# DUE_shield.net
KiCad netlist of a schematic drawn in EAGLE
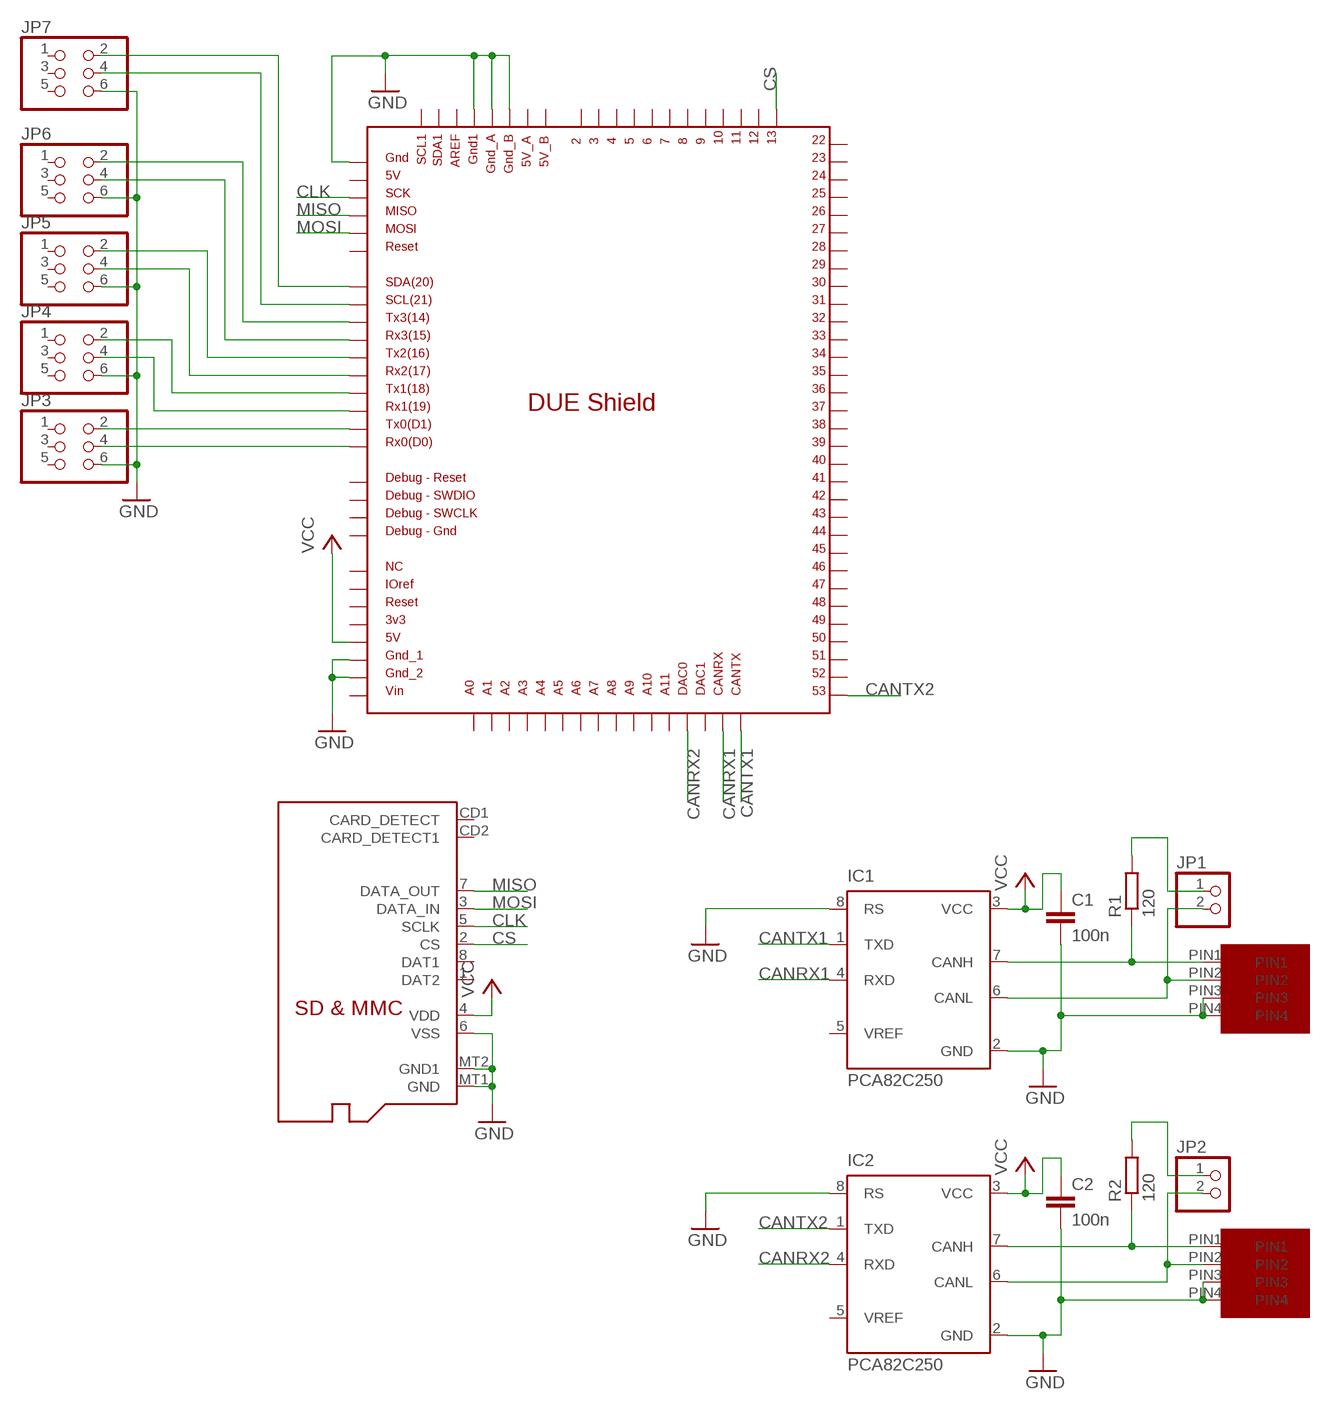
[diagram p0: schematic, sheet 1]

(export (version "E")
  (design (tool "Eeschema 10.0.6"))
  (components
    (comp (ref "C1")
      (value "100n")
      (footprint "eagle-import:C050-024X044")
      (libsource (lib "eagle-import") (part "C-EU050-024X044"))
    )
    (comp (ref "C2")
      (value "100n")
      (footprint "eagle-import:C050-024X044")
      (libsource (lib "eagle-import") (part "C-EU050-024X044"))
    )
    (comp (ref "IC1")
      (value "PCA82C250")
      (footprint "eagle-import:DIL08")
      (libsource (lib "eagle-import") (part "PCA82C250"))
    )
    (comp (ref "IC2")
      (value "PCA82C250")
      (footprint "eagle-import:DIL08")
      (libsource (lib "eagle-import") (part "PCA82C250"))
    )
    (comp (ref "JP1")
      (value "PINHD-1X2")
      (footprint "eagle-import:1X02")
      (libsource (lib "eagle-import") (part "PINHD-1X2"))
    )
    (comp (ref "JP2")
      (value "PINHD-1X2")
      (footprint "eagle-import:1X02")
      (libsource (lib "eagle-import") (part "PINHD-1X2"))
    )
    (comp (ref "JP3")
      (value "PINHD-2X3")
      (footprint "eagle-import:2X03")
      (libsource (lib "eagle-import") (part "PINHD-2X3"))
    )
    (comp (ref "JP4")
      (value "PINHD-2X3")
      (footprint "eagle-import:2X03")
      (libsource (lib "eagle-import") (part "PINHD-2X3"))
    )
    (comp (ref "JP5")
      (value "PINHD-2X3")
      (footprint "eagle-import:2X03")
      (libsource (lib "eagle-import") (part "PINHD-2X3"))
    )
    (comp (ref "JP6")
      (value "PINHD-2X3")
      (footprint "eagle-import:2X03")
      (libsource (lib "eagle-import") (part "PINHD-2X3"))
    )
    (comp (ref "JP7")
      (value "PINHD-2X3")
      (footprint "eagle-import:2X03")
      (libsource (lib "eagle-import") (part "PINHD-2X3"))
    )
    (comp (ref "R1")
      (value "120")
      (footprint "eagle-import:0204_7")
      (libsource (lib "eagle-import") (part "R-EU_0204/7"))
    )
    (comp (ref "R2")
      (value "120")
      (footprint "eagle-import:0204_7")
      (libsource (lib "eagle-import") (part "R-EU_0204/7"))
    )
    (comp (ref "U$1")
      (value "DUE(NORMAL)")
      (footprint "eagle-import:DUE(NORMAL)")
      (libsource (lib "eagle-import") (part "DUE(NORMAL)"))
    )
    (comp (ref "U$2")
      (value "MICROFIT4")
      (footprint "eagle-import:MICROFIT4SOCK")
      (libsource (lib "eagle-import") (part "MICROFIT4"))
    )
    (comp (ref "U$3")
      (value "MICROFIT4")
      (footprint "eagle-import:MICROFIT4SOCK")
      (libsource (lib "eagle-import") (part "MICROFIT4"))
    )
    (comp (ref "U$4")
      (value "MICROSD")
      (footprint "eagle-import:MICROSD")
      (libsource (lib "eagle-import") (part "MICROSD"))
    )
  )
  (nets
    (net (code "1") (name "/CANRX1") (class "Default")
      (node (ref "IC1") (pin "4") (pinfunction "RXD_4") (pintype "output"))
      (node (ref "U$1") (pin "CANRX") (pinfunction "CANRX_CANRX") (pintype "bidirectional"))
    )
    (net (code "2") (name "/CANRX2") (class "Default")
      (node (ref "IC2") (pin "4") (pinfunction "RXD_4") (pintype "output"))
      (node (ref "U$1") (pin "DAC0") (pinfunction "DAC0_DAC0") (pintype "bidirectional"))
    )
    (net (code "3") (name "/CANTX1") (class "Default")
      (node (ref "IC1") (pin "1") (pinfunction "TXD_1") (pintype "input"))
      (node (ref "U$1") (pin "CANTX") (pinfunction "CANTX_CANTX") (pintype "bidirectional"))
    )
    (net (code "4") (name "/CANTX2") (class "Default")
      (node (ref "IC2") (pin "1") (pinfunction "TXD_1") (pintype "input"))
      (node (ref "U$1") (pin "53") (pinfunction "53_53") (pintype "bidirectional"))
    )
    (net (code "5") (name "/CLK") (class "Default")
      (node (ref "U$1") (pin "SCK_ICSP") (pinfunction "SCK_ICSP_SCK_ICSP") (pintype "bidirectional"))
      (node (ref "U$4") (pin "5") (pinfunction "SCLK_5") (pintype "input"))
    )
    (net (code "6") (name "/CS") (class "Default")
      (node (ref "U$1") (pin "13") (pinfunction "13_13") (pintype "bidirectional"))
      (node (ref "U$4") (pin "2") (pinfunction "CS_2") (pintype "input"))
    )
    (net (code "7") (name "/MISO") (class "Default")
      (node (ref "U$1") (pin "MISO_ICSP") (pinfunction "MISO_ICSP_MISO_ICSP") (pintype "bidirectional"))
      (node (ref "U$4") (pin "7") (pinfunction "DATA_OUT_7") (pintype "output"))
    )
    (net (code "8") (name "/MOSI") (class "Default")
      (node (ref "U$1") (pin "MOSI_ICSP") (pinfunction "MOSI_ICSP_MOSI_ICSP") (pintype "bidirectional"))
      (node (ref "U$4") (pin "3") (pinfunction "DATA_IN_3") (pintype "input"))
    )
    (net (code "9") (name "GND") (class "Default")
      (node (ref "C1") (pin "2") (pinfunction "2_2") (pintype "passive"))
      (node (ref "C2") (pin "2") (pinfunction "2_2") (pintype "passive"))
      (node (ref "IC1") (pin "2") (pinfunction "GND_2") (pintype "power_in"))
      (node (ref "IC1") (pin "8") (pinfunction "RS_8") (pintype "input"))
      (node (ref "IC2") (pin "2") (pinfunction "GND_2") (pintype "power_in"))
      (node (ref "IC2") (pin "8") (pinfunction "RS_8") (pintype "input"))
      (node (ref "JP3") (pin "6") (pinfunction "6_6") (pintype "passive"))
      (node (ref "JP4") (pin "6") (pinfunction "6_6") (pintype "passive"))
      (node (ref "JP5") (pin "6") (pinfunction "6_6") (pintype "passive"))
      (node (ref "JP6") (pin "6") (pinfunction "6_6") (pintype "passive"))
      (node (ref "JP7") (pin "6") (pinfunction "6_6") (pintype "passive"))
      (node (ref "U$1") (pin "5V_ICSP") (pinfunction "5V_ICSP_5V_ICSP") (pintype "bidirectional"))
      (node (ref "U$1") (pin "GND1") (pinfunction "GND1_GND1") (pintype "bidirectional"))
      (node (ref "U$1") (pin "GND_1") (pinfunction "GND_1_GND_1") (pintype "bidirectional"))
      (node (ref "U$1") (pin "GND_2") (pinfunction "GND_2_GND_2") (pintype "bidirectional"))
      (node (ref "U$1") (pin "GND_A") (pinfunction "GND_A_GND_A") (pintype "bidirectional"))
      (node (ref "U$1") (pin "GND_B") (pinfunction "GND_B_GND_B") (pintype "bidirectional"))
      (node (ref "U$2") (pin "PIN3") (pinfunction "PIN3_PIN3") (pintype "bidirectional"))
      (node (ref "U$2") (pin "PIN4") (pinfunction "PIN4_PIN4") (pintype "bidirectional"))
      (node (ref "U$3") (pin "PIN3") (pinfunction "PIN3_PIN3") (pintype "bidirectional"))
      (node (ref "U$3") (pin "PIN4") (pinfunction "PIN4_PIN4") (pintype "bidirectional"))
      (node (ref "U$4") (pin "6") (pinfunction "VSS_6") (pintype "power_in"))
      (node (ref "U$4") (pin "MT1") (pinfunction "GND_MT1") (pintype "power_in"))
      (node (ref "U$4") (pin "MT2") (pinfunction "GND1_MT2") (pintype "power_in"))
    )
    (net (code "10") (name "Net-(IC1-CANH)") (class "Default")
      (node (ref "IC1") (pin "7") (pinfunction "CANH_7") (pintype "bidirectional"))
      (node (ref "R1") (pin "1") (pinfunction "1_1") (pintype "passive"))
      (node (ref "U$2") (pin "PIN1") (pinfunction "PIN1_PIN1") (pintype "bidirectional"))
    )
    (net (code "11") (name "Net-(IC1-CANL)") (class "Default")
      (node (ref "IC1") (pin "6") (pinfunction "CANL_6") (pintype "bidirectional"))
      (node (ref "JP1") (pin "2") (pinfunction "2_2") (pintype "passive"))
      (node (ref "U$2") (pin "PIN2") (pinfunction "PIN2_PIN2") (pintype "bidirectional"))
    )
    (net (code "12") (name "Net-(IC2-CANH)") (class "Default")
      (node (ref "IC2") (pin "7") (pinfunction "CANH_7") (pintype "bidirectional"))
      (node (ref "R2") (pin "1") (pinfunction "1_1") (pintype "passive"))
      (node (ref "U$3") (pin "PIN1") (pinfunction "PIN1_PIN1") (pintype "bidirectional"))
    )
    (net (code "13") (name "Net-(IC2-CANL)") (class "Default")
      (node (ref "IC2") (pin "6") (pinfunction "CANL_6") (pintype "bidirectional"))
      (node (ref "JP2") (pin "2") (pinfunction "2_2") (pintype "passive"))
      (node (ref "U$3") (pin "PIN2") (pinfunction "PIN2_PIN2") (pintype "bidirectional"))
    )
    (net (code "14") (name "Net-(JP1-Pad1)") (class "Default")
      (node (ref "JP1") (pin "1") (pinfunction "1_1") (pintype "passive"))
      (node (ref "R1") (pin "2") (pinfunction "2_2") (pintype "passive"))
    )
    (net (code "15") (name "Net-(JP2-Pad1)") (class "Default")
      (node (ref "JP2") (pin "1") (pinfunction "1_1") (pintype "passive"))
      (node (ref "R2") (pin "2") (pinfunction "2_2") (pintype "passive"))
    )
    (net (code "16") (name "Net-(JP3-Pad2)") (class "Default")
      (node (ref "JP3") (pin "2") (pinfunction "2_2") (pintype "passive"))
      (node (ref "U$1") (pin "TX0") (pinfunction "TX0_TX0") (pintype "bidirectional"))
    )
    (net (code "17") (name "Net-(JP3-Pad4)") (class "Default")
      (node (ref "JP3") (pin "4") (pinfunction "4_4") (pintype "passive"))
      (node (ref "U$1") (pin "RX0") (pinfunction "RX0_RX0") (pintype "bidirectional"))
    )
    (net (code "18") (name "Net-(JP4-Pad2)") (class "Default")
      (node (ref "JP4") (pin "2") (pinfunction "2_2") (pintype "passive"))
      (node (ref "U$1") (pin "TX1") (pinfunction "TX1_TX1") (pintype "bidirectional"))
    )
    (net (code "19") (name "Net-(JP4-Pad4)") (class "Default")
      (node (ref "JP4") (pin "4") (pinfunction "4_4") (pintype "passive"))
      (node (ref "U$1") (pin "RX1") (pinfunction "RX1_RX1") (pintype "bidirectional"))
    )
    (net (code "20") (name "Net-(JP5-Pad2)") (class "Default")
      (node (ref "JP5") (pin "2") (pinfunction "2_2") (pintype "passive"))
      (node (ref "U$1") (pin "TX2") (pinfunction "TX2_TX2") (pintype "bidirectional"))
    )
    (net (code "21") (name "Net-(JP5-Pad4)") (class "Default")
      (node (ref "JP5") (pin "4") (pinfunction "4_4") (pintype "passive"))
      (node (ref "U$1") (pin "RX2") (pinfunction "RX2_RX2") (pintype "bidirectional"))
    )
    (net (code "22") (name "Net-(JP6-Pad2)") (class "Default")
      (node (ref "JP6") (pin "2") (pinfunction "2_2") (pintype "passive"))
      (node (ref "U$1") (pin "TX3") (pinfunction "TX3_TX3") (pintype "bidirectional"))
    )
    (net (code "23") (name "Net-(JP6-Pad4)") (class "Default")
      (node (ref "JP6") (pin "4") (pinfunction "4_4") (pintype "passive"))
      (node (ref "U$1") (pin "RX3") (pinfunction "RX3_RX3") (pintype "bidirectional"))
    )
    (net (code "24") (name "Net-(JP7-Pad2)") (class "Default")
      (node (ref "JP7") (pin "2") (pinfunction "2_2") (pintype "passive"))
      (node (ref "U$1") (pin "SDA") (pinfunction "SDA_SDA") (pintype "bidirectional"))
    )
    (net (code "25") (name "Net-(JP7-Pad4)") (class "Default")
      (node (ref "JP7") (pin "4") (pinfunction "4_4") (pintype "passive"))
      (node (ref "U$1") (pin "SCL") (pinfunction "SCL_SCL") (pintype "bidirectional"))
    )
    (net (code "26") (name "VCC") (class "Default")
      (node (ref "C1") (pin "1") (pinfunction "1_1") (pintype "passive"))
      (node (ref "C2") (pin "1") (pinfunction "1_1") (pintype "passive"))
      (node (ref "IC1") (pin "3") (pinfunction "VCC_3") (pintype "power_in"))
      (node (ref "IC2") (pin "3") (pinfunction "VCC_3") (pintype "power_in"))
      (node (ref "U$1") (pin "5V") (pinfunction "5V_5V") (pintype "bidirectional"))
      (node (ref "U$4") (pin "4") (pinfunction "VDD_4") (pintype "power_in"))
    )
    (net (code "27") (name "unconnected-(IC1-VREF-Pad5)") (class "Default")
      (node (ref "IC1") (pin "5") (pinfunction "VREF_5") (pintype "output"))
    )
    (net (code "28") (name "unconnected-(IC2-VREF-Pad5)") (class "Default")
      (node (ref "IC2") (pin "5") (pinfunction "VREF_5") (pintype "output"))
    )
    (net (code "29") (name "unconnected-(JP3-Pad1)") (class "Default")
      (node (ref "JP3") (pin "1") (pinfunction "1_1") (pintype "passive"))
    )
    (net (code "30") (name "unconnected-(JP3-Pad3)") (class "Default")
      (node (ref "JP3") (pin "3") (pinfunction "3_3") (pintype "passive"))
    )
    (net (code "31") (name "unconnected-(JP3-Pad5)") (class "Default")
      (node (ref "JP3") (pin "5") (pinfunction "5_5") (pintype "passive"))
    )
    (net (code "32") (name "unconnected-(JP4-Pad1)") (class "Default")
      (node (ref "JP4") (pin "1") (pinfunction "1_1") (pintype "passive"))
    )
    (net (code "33") (name "unconnected-(JP4-Pad3)") (class "Default")
      (node (ref "JP4") (pin "3") (pinfunction "3_3") (pintype "passive"))
    )
    (net (code "34") (name "unconnected-(JP4-Pad5)") (class "Default")
      (node (ref "JP4") (pin "5") (pinfunction "5_5") (pintype "passive"))
    )
    (net (code "35") (name "unconnected-(JP5-Pad1)") (class "Default")
      (node (ref "JP5") (pin "1") (pinfunction "1_1") (pintype "passive"))
    )
    (net (code "36") (name "unconnected-(JP5-Pad3)") (class "Default")
      (node (ref "JP5") (pin "3") (pinfunction "3_3") (pintype "passive"))
    )
    (net (code "37") (name "unconnected-(JP5-Pad5)") (class "Default")
      (node (ref "JP5") (pin "5") (pinfunction "5_5") (pintype "passive"))
    )
    (net (code "38") (name "unconnected-(JP6-Pad1)") (class "Default")
      (node (ref "JP6") (pin "1") (pinfunction "1_1") (pintype "passive"))
    )
    (net (code "39") (name "unconnected-(JP6-Pad3)") (class "Default")
      (node (ref "JP6") (pin "3") (pinfunction "3_3") (pintype "passive"))
    )
    (net (code "40") (name "unconnected-(JP6-Pad5)") (class "Default")
      (node (ref "JP6") (pin "5") (pinfunction "5_5") (pintype "passive"))
    )
    (net (code "41") (name "unconnected-(JP7-Pad1)") (class "Default")
      (node (ref "JP7") (pin "1") (pinfunction "1_1") (pintype "passive"))
    )
    (net (code "42") (name "unconnected-(JP7-Pad3)") (class "Default")
      (node (ref "JP7") (pin "3") (pinfunction "3_3") (pintype "passive"))
    )
    (net (code "43") (name "unconnected-(JP7-Pad5)") (class "Default")
      (node (ref "JP7") (pin "5") (pinfunction "5_5") (pintype "passive"))
    )
    (net (code "44") (name "unconnected-(U$1-Pad2)") (class "Default")
      (node (ref "U$1") (pin "2") (pinfunction "2_2") (pintype "bidirectional"))
    )
    (net (code "45") (name "unconnected-(U$1-Pad3)") (class "Default")
      (node (ref "U$1") (pin "3") (pinfunction "3_3") (pintype "bidirectional"))
    )
    (net (code "46") (name "unconnected-(U$1-Pad3V3)") (class "Default")
      (node (ref "U$1") (pin "3V3") (pinfunction "3V3_3V3") (pintype "bidirectional"))
    )
    (net (code "47") (name "unconnected-(U$1-Pad4)") (class "Default")
      (node (ref "U$1") (pin "4") (pinfunction "4_4") (pintype "bidirectional"))
    )
    (net (code "48") (name "unconnected-(U$1-Pad5)") (class "Default")
      (node (ref "U$1") (pin "5") (pinfunction "5_5") (pintype "bidirectional"))
    )
    (net (code "49") (name "unconnected-(U$1-Pad5V_A)") (class "Default")
      (node (ref "U$1") (pin "5V_A") (pinfunction "5V_A_5V_A") (pintype "bidirectional"))
    )
    (net (code "50") (name "unconnected-(U$1-Pad5V_B)") (class "Default")
      (node (ref "U$1") (pin "5V_B") (pinfunction "5V_B_5V_B") (pintype "bidirectional"))
    )
    (net (code "51") (name "unconnected-(U$1-Pad6)") (class "Default")
      (node (ref "U$1") (pin "6") (pinfunction "6_6") (pintype "bidirectional"))
    )
    (net (code "52") (name "unconnected-(U$1-Pad7)") (class "Default")
      (node (ref "U$1") (pin "7") (pinfunction "7_7") (pintype "bidirectional"))
    )
    (net (code "53") (name "unconnected-(U$1-Pad8)") (class "Default")
      (node (ref "U$1") (pin "8") (pinfunction "8_8") (pintype "bidirectional"))
    )
    (net (code "54") (name "unconnected-(U$1-Pad9)") (class "Default")
      (node (ref "U$1") (pin "9") (pinfunction "9_9") (pintype "bidirectional"))
    )
    (net (code "55") (name "unconnected-(U$1-Pad10)") (class "Default")
      (node (ref "U$1") (pin "10") (pinfunction "10_10") (pintype "bidirectional"))
    )
    (net (code "56") (name "unconnected-(U$1-Pad11)") (class "Default")
      (node (ref "U$1") (pin "11") (pinfunction "11_11") (pintype "bidirectional"))
    )
    (net (code "57") (name "unconnected-(U$1-Pad12)") (class "Default")
      (node (ref "U$1") (pin "12") (pinfunction "12_12") (pintype "bidirectional"))
    )
    (net (code "58") (name "unconnected-(U$1-Pad22)") (class "Default")
      (node (ref "U$1") (pin "22") (pinfunction "22_22") (pintype "bidirectional"))
    )
    (net (code "59") (name "unconnected-(U$1-Pad23)") (class "Default")
      (node (ref "U$1") (pin "23") (pinfunction "23_23") (pintype "bidirectional"))
    )
    (net (code "60") (name "unconnected-(U$1-Pad24)") (class "Default")
      (node (ref "U$1") (pin "24") (pinfunction "24_24") (pintype "bidirectional"))
    )
    (net (code "61") (name "unconnected-(U$1-Pad25)") (class "Default")
      (node (ref "U$1") (pin "25") (pinfunction "25_25") (pintype "bidirectional"))
    )
    (net (code "62") (name "unconnected-(U$1-Pad26)") (class "Default")
      (node (ref "U$1") (pin "26") (pinfunction "26_26") (pintype "bidirectional"))
    )
    (net (code "63") (name "unconnected-(U$1-Pad27)") (class "Default")
      (node (ref "U$1") (pin "27") (pinfunction "27_27") (pintype "bidirectional"))
    )
    (net (code "64") (name "unconnected-(U$1-Pad28)") (class "Default")
      (node (ref "U$1") (pin "28") (pinfunction "28_28") (pintype "bidirectional"))
    )
    (net (code "65") (name "unconnected-(U$1-Pad29)") (class "Default")
      (node (ref "U$1") (pin "29") (pinfunction "29_29") (pintype "bidirectional"))
    )
    (net (code "66") (name "unconnected-(U$1-Pad30)") (class "Default")
      (node (ref "U$1") (pin "30") (pinfunction "30_30") (pintype "bidirectional"))
    )
    (net (code "67") (name "unconnected-(U$1-Pad31)") (class "Default")
      (node (ref "U$1") (pin "31") (pinfunction "31_31") (pintype "bidirectional"))
    )
    (net (code "68") (name "unconnected-(U$1-Pad32)") (class "Default")
      (node (ref "U$1") (pin "32") (pinfunction "32_32") (pintype "bidirectional"))
    )
    (net (code "69") (name "unconnected-(U$1-Pad33)") (class "Default")
      (node (ref "U$1") (pin "33") (pinfunction "33_33") (pintype "bidirectional"))
    )
    (net (code "70") (name "unconnected-(U$1-Pad34)") (class "Default")
      (node (ref "U$1") (pin "34") (pinfunction "34_34") (pintype "bidirectional"))
    )
    (net (code "71") (name "unconnected-(U$1-Pad35)") (class "Default")
      (node (ref "U$1") (pin "35") (pinfunction "35_35") (pintype "bidirectional"))
    )
    (net (code "72") (name "unconnected-(U$1-Pad36)") (class "Default")
      (node (ref "U$1") (pin "36") (pinfunction "36_36") (pintype "bidirectional"))
    )
    (net (code "73") (name "unconnected-(U$1-Pad37)") (class "Default")
      (node (ref "U$1") (pin "37") (pinfunction "37_37") (pintype "bidirectional"))
    )
    (net (code "74") (name "unconnected-(U$1-Pad38)") (class "Default")
      (node (ref "U$1") (pin "38") (pinfunction "38_38") (pintype "bidirectional"))
    )
    (net (code "75") (name "unconnected-(U$1-Pad39)") (class "Default")
      (node (ref "U$1") (pin "39") (pinfunction "39_39") (pintype "bidirectional"))
    )
    (net (code "76") (name "unconnected-(U$1-Pad40)") (class "Default")
      (node (ref "U$1") (pin "40") (pinfunction "40_40") (pintype "bidirectional"))
    )
    (net (code "77") (name "unconnected-(U$1-Pad41)") (class "Default")
      (node (ref "U$1") (pin "41") (pinfunction "41_41") (pintype "bidirectional"))
    )
    (net (code "78") (name "unconnected-(U$1-Pad42)") (class "Default")
      (node (ref "U$1") (pin "42") (pinfunction "42_42") (pintype "bidirectional"))
    )
    (net (code "79") (name "unconnected-(U$1-Pad43)") (class "Default")
      (node (ref "U$1") (pin "43") (pinfunction "43_43") (pintype "bidirectional"))
    )
    (net (code "80") (name "unconnected-(U$1-Pad44)") (class "Default")
      (node (ref "U$1") (pin "44") (pinfunction "44_44") (pintype "bidirectional"))
    )
    (net (code "81") (name "unconnected-(U$1-Pad45)") (class "Default")
      (node (ref "U$1") (pin "45") (pinfunction "45_45") (pintype "bidirectional"))
    )
    (net (code "82") (name "unconnected-(U$1-Pad46)") (class "Default")
      (node (ref "U$1") (pin "46") (pinfunction "46_46") (pintype "bidirectional"))
    )
    (net (code "83") (name "unconnected-(U$1-Pad47)") (class "Default")
      (node (ref "U$1") (pin "47") (pinfunction "47_47") (pintype "bidirectional"))
    )
    (net (code "84") (name "unconnected-(U$1-Pad48)") (class "Default")
      (node (ref "U$1") (pin "48") (pinfunction "48_48") (pintype "bidirectional"))
    )
    (net (code "85") (name "unconnected-(U$1-Pad49)") (class "Default")
      (node (ref "U$1") (pin "49") (pinfunction "49_49") (pintype "bidirectional"))
    )
    (net (code "86") (name "unconnected-(U$1-Pad50)") (class "Default")
      (node (ref "U$1") (pin "50") (pinfunction "50_50") (pintype "bidirectional"))
    )
    (net (code "87") (name "unconnected-(U$1-Pad51)") (class "Default")
      (node (ref "U$1") (pin "51") (pinfunction "51_51") (pintype "bidirectional"))
    )
    (net (code "88") (name "unconnected-(U$1-Pad52)") (class "Default")
      (node (ref "U$1") (pin "52") (pinfunction "52_52") (pintype "bidirectional"))
    )
    (net (code "89") (name "unconnected-(U$1-PadA0)") (class "Default")
      (node (ref "U$1") (pin "A0") (pinfunction "A0_A0") (pintype "bidirectional"))
    )
    (net (code "90") (name "unconnected-(U$1-PadA1)") (class "Default")
      (node (ref "U$1") (pin "A1") (pinfunction "A1_A1") (pintype "bidirectional"))
    )
    (net (code "91") (name "unconnected-(U$1-PadA2)") (class "Default")
      (node (ref "U$1") (pin "A2") (pinfunction "A2_A2") (pintype "bidirectional"))
    )
    (net (code "92") (name "unconnected-(U$1-PadA3)") (class "Default")
      (node (ref "U$1") (pin "A3") (pinfunction "A3_A3") (pintype "bidirectional"))
    )
    (net (code "93") (name "unconnected-(U$1-PadA4)") (class "Default")
      (node (ref "U$1") (pin "A4") (pinfunction "A4_A4") (pintype "bidirectional"))
    )
    (net (code "94") (name "unconnected-(U$1-PadA5)") (class "Default")
      (node (ref "U$1") (pin "A5") (pinfunction "A5_A5") (pintype "bidirectional"))
    )
    (net (code "95") (name "unconnected-(U$1-PadA6)") (class "Default")
      (node (ref "U$1") (pin "A6") (pinfunction "A6_A6") (pintype "bidirectional"))
    )
    (net (code "96") (name "unconnected-(U$1-PadA7)") (class "Default")
      (node (ref "U$1") (pin "A7") (pinfunction "A7_A7") (pintype "bidirectional"))
    )
    (net (code "97") (name "unconnected-(U$1-PadA8)") (class "Default")
      (node (ref "U$1") (pin "A8") (pinfunction "A8_A8") (pintype "bidirectional"))
    )
    (net (code "98") (name "unconnected-(U$1-PadA9)") (class "Default")
      (node (ref "U$1") (pin "A9") (pinfunction "A9_A9") (pintype "bidirectional"))
    )
    (net (code "99") (name "unconnected-(U$1-PadA10)") (class "Default")
      (node (ref "U$1") (pin "A10") (pinfunction "A10_A10") (pintype "bidirectional"))
    )
    (net (code "100") (name "unconnected-(U$1-PadA11)") (class "Default")
      (node (ref "U$1") (pin "A11") (pinfunction "A11_A11") (pintype "bidirectional"))
    )
    (net (code "101") (name "unconnected-(U$1-PadAREF)") (class "Default")
      (node (ref "U$1") (pin "AREF") (pinfunction "AREF_AREF") (pintype "bidirectional"))
    )
    (net (code "102") (name "unconnected-(U$1-PadDAC1)") (class "Default")
      (node (ref "U$1") (pin "DAC1") (pinfunction "DAC1_DAC1") (pintype "bidirectional"))
    )
    (net (code "103") (name "unconnected-(U$1-PadGND_DEBUG)") (class "Default")
      (node (ref "U$1") (pin "GND_DEBUG") (pinfunction "GND_DEBUG_GND_DEBUG") (pintype "bidirectional"))
    )
    (net (code "104") (name "unconnected-(U$1-PadGND_ICSP)") (class "Default")
      (node (ref "U$1") (pin "GND_ICSP") (pinfunction "GND_ICSP_GND_ICSP") (pintype "bidirectional"))
    )
    (net (code "105") (name "unconnected-(U$1-PadIOREF)") (class "Default")
      (node (ref "U$1") (pin "IOREF") (pinfunction "IOREF_IOREF") (pintype "bidirectional"))
    )
    (net (code "106") (name "unconnected-(U$1-PadNC)") (class "Default")
      (node (ref "U$1") (pin "NC") (pinfunction "NC_NC") (pintype "bidirectional"))
    )
    (net (code "107") (name "unconnected-(U$1-PadRESET)") (class "Default")
      (node (ref "U$1") (pin "RESET") (pinfunction "RESET_RESET") (pintype "bidirectional"))
    )
    (net (code "108") (name "unconnected-(U$1-PadRESET_DEBUG)") (class "Default")
      (node (ref "U$1") (pin "RESET_DEBUG") (pinfunction "RESET_DEBUG_RESET_DEBUG") (pintype "bidirectional"))
    )
    (net (code "109") (name "unconnected-(U$1-PadRESET_ICSP)") (class "Default")
      (node (ref "U$1") (pin "RESET_ICSP") (pinfunction "RESET_ICSP_RESET_ICSP") (pintype "bidirectional"))
    )
    (net (code "110") (name "unconnected-(U$1-PadSCL1)") (class "Default")
      (node (ref "U$1") (pin "SCL1") (pinfunction "SCL1_SCL1") (pintype "bidirectional"))
    )
    (net (code "111") (name "unconnected-(U$1-PadSDA1)") (class "Default")
      (node (ref "U$1") (pin "SDA1") (pinfunction "SDA1_SDA1") (pintype "bidirectional"))
    )
    (net (code "112") (name "unconnected-(U$1-PadSWCLK_DEBUG)") (class "Default")
      (node (ref "U$1") (pin "SWCLK_DEBUG") (pinfunction "SWCLK_DEBUG_SWCLK_DEBUG") (pintype "bidirectional"))
    )
    (net (code "113") (name "unconnected-(U$1-PadSWDIO_DEBUG)") (class "Default")
      (node (ref "U$1") (pin "SWDIO_DEBUG") (pinfunction "SWDIO_DEBUG_SWDIO_DEBUG") (pintype "bidirectional"))
    )
    (net (code "114") (name "unconnected-(U$1-PadVIN)") (class "Default")
      (node (ref "U$1") (pin "VIN") (pinfunction "VIN_VIN") (pintype "bidirectional"))
    )
    (net (code "115") (name "unconnected-(U$4-CARD_DETECT-PadCD1)") (class "Default")
      (node (ref "U$4") (pin "CD1") (pinfunction "CARD_DETECT_CD1") (pintype "passive"))
    )
    (net (code "116") (name "unconnected-(U$4-CARD_DETECT1-PadCD2)") (class "Default")
      (node (ref "U$4") (pin "CD2") (pinfunction "CARD_DETECT1_CD2") (pintype "passive"))
    )
    (net (code "117") (name "unconnected-(U$4-DAT1-Pad8)") (class "Default")
      (node (ref "U$4") (pin "8") (pinfunction "DAT1_8") (pintype "bidirectional"))
    )
    (net (code "118") (name "unconnected-(U$4-DAT2-Pad1)") (class "Default")
      (node (ref "U$4") (pin "1") (pinfunction "DAT2_1") (pintype "bidirectional"))
    )
  )
)
